# covid-respirator-ProtoB.net
KiCad netlist of a schematic drawn in EAGLE
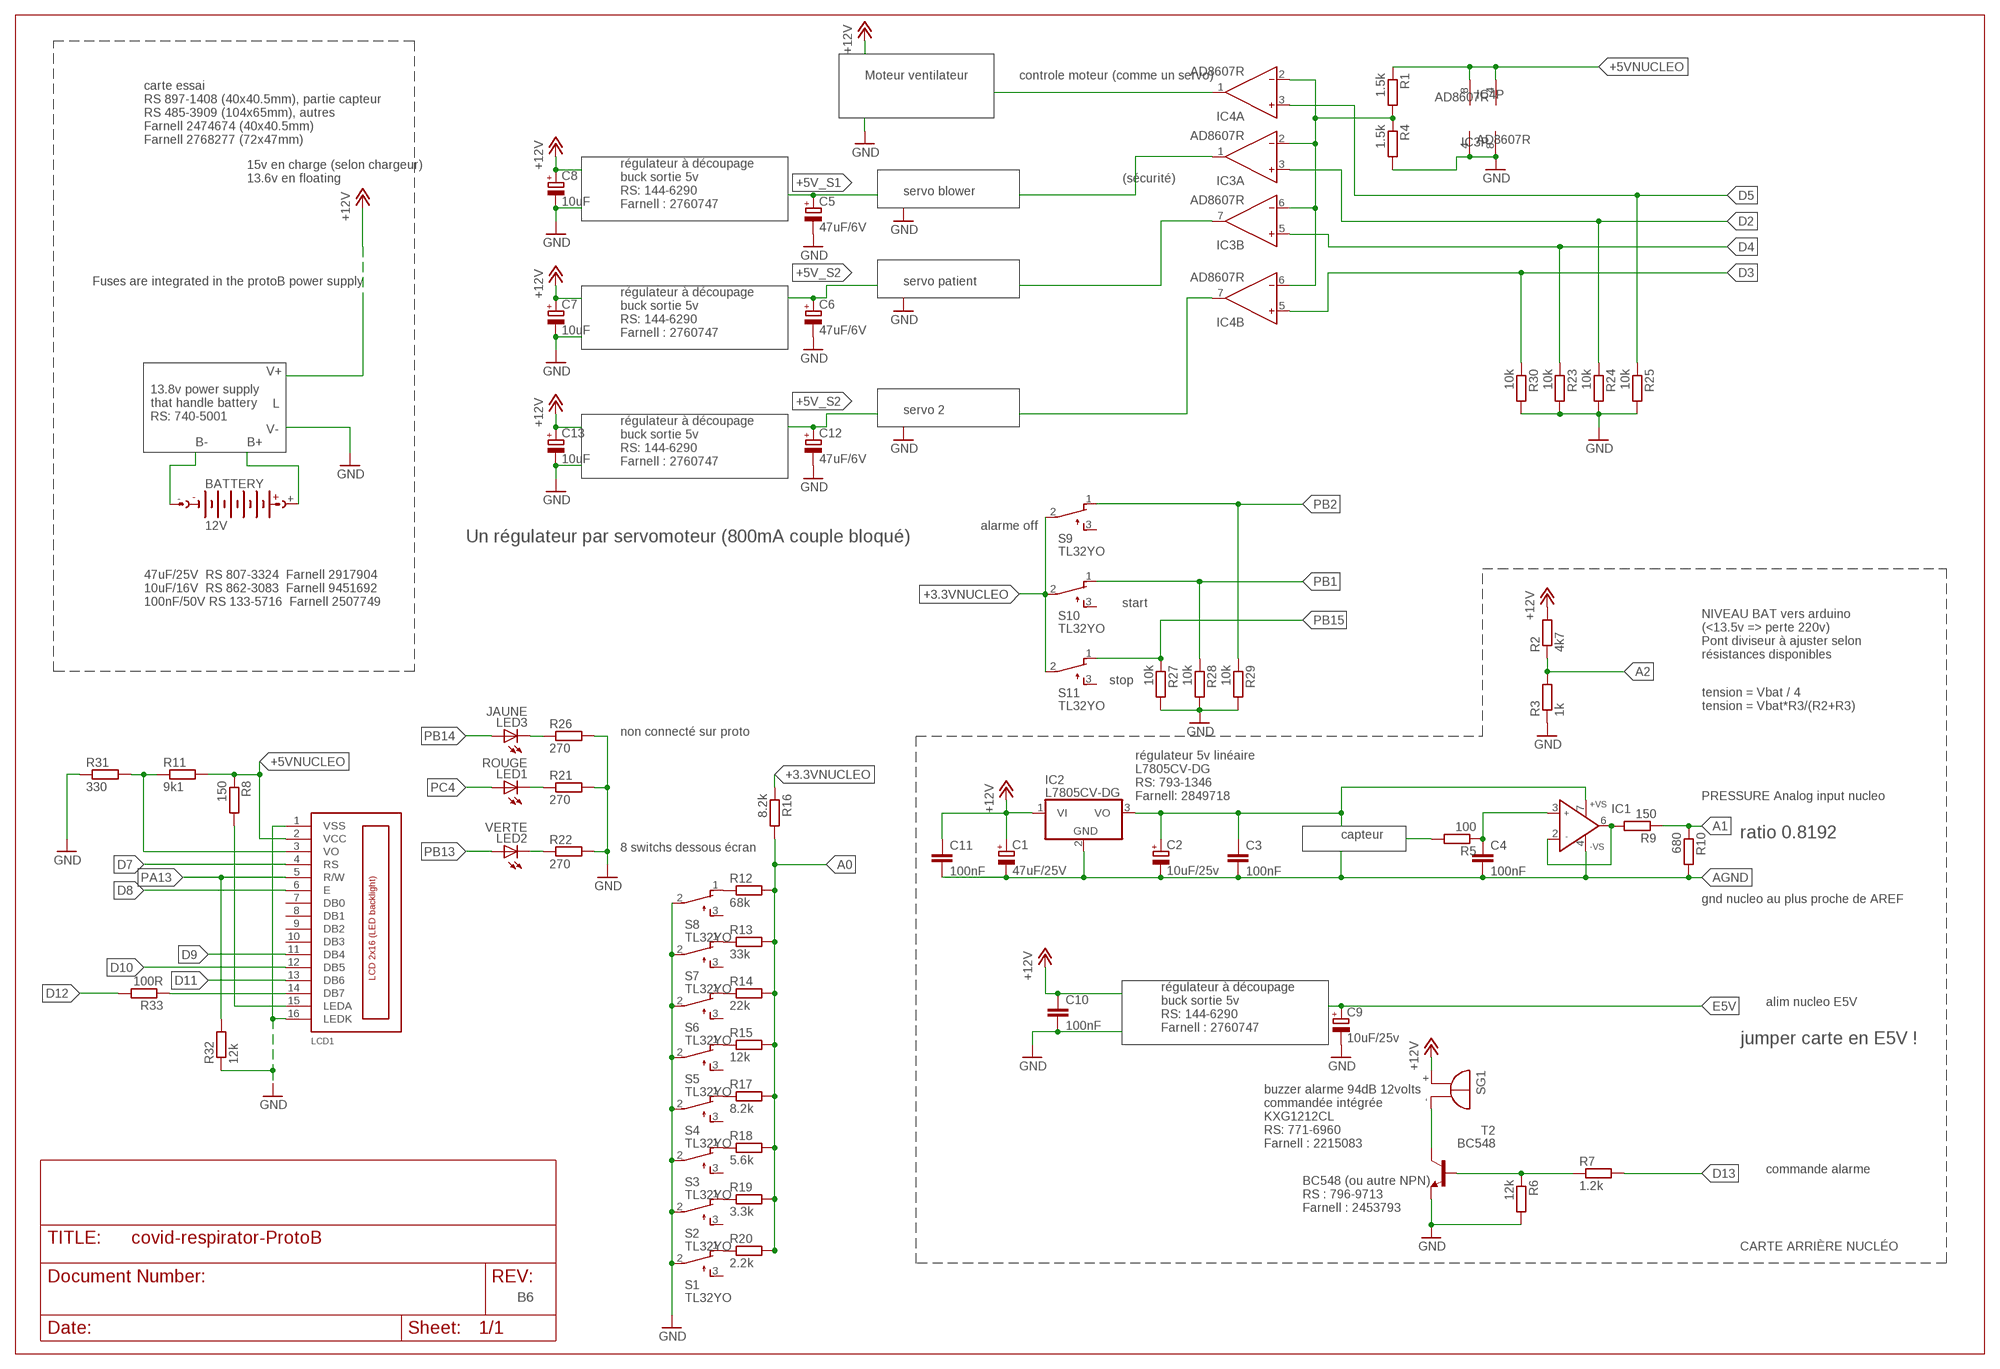
[diagram p0: schematic, sheet 1]

(export (version "E")
  (design (tool "Eeschema 10.0.6"))
  (components
    (comp (ref "BATTERY")
      (value "12V")
      (footprint "eagle-import:AB9V")
      (libsource (lib "eagle-import") (part "AB9V"))
    )
    (comp (ref "C1")
      (value "47uF/25V")
      (footprint "eagle-import:150CLZ-1010")
      (libsource (lib "eagle-import") (part "CPOL-EU150CLZ-1010"))
    )
    (comp (ref "C2")
      (value "10uF/25v")
      (footprint "eagle-import:150CLZ-1010")
      (libsource (lib "eagle-import") (part "CPOL-EU150CLZ-1010"))
    )
    (comp (ref "C3")
      (value "100nF")
      (footprint "eagle-import:C050-050X075")
      (libsource (lib "eagle-import") (part "C-EU050-050X075"))
    )
    (comp (ref "C4")
      (value "100nF")
      (footprint "eagle-import:C050-050X075")
      (libsource (lib "eagle-import") (part "C-EU050-050X075"))
    )
    (comp (ref "C5")
      (value "47uF/6V")
      (footprint "eagle-import:150CLZ-1010")
      (libsource (lib "eagle-import") (part "CPOL-EU150CLZ-1010"))
    )
    (comp (ref "C6")
      (value "47uF/6V")
      (footprint "eagle-import:150CLZ-1010")
      (libsource (lib "eagle-import") (part "CPOL-EU150CLZ-1010"))
    )
    (comp (ref "C7")
      (value "10uF")
      (footprint "eagle-import:150CLZ-1010")
      (libsource (lib "eagle-import") (part "CPOL-EU150CLZ-1010"))
    )
    (comp (ref "C8")
      (value "10uF")
      (footprint "eagle-import:150CLZ-1010")
      (libsource (lib "eagle-import") (part "CPOL-EU150CLZ-1010"))
    )
    (comp (ref "C9")
      (value "10uF/25v")
      (footprint "eagle-import:150CLZ-1010")
      (libsource (lib "eagle-import") (part "CPOL-EU150CLZ-1010"))
    )
    (comp (ref "C10")
      (value "100nF")
      (footprint "eagle-import:C050-050X075")
      (libsource (lib "eagle-import") (part "C-EU050-050X075"))
    )
    (comp (ref "C11")
      (value "100nF")
      (footprint "eagle-import:C050-050X075")
      (libsource (lib "eagle-import") (part "C-EU050-050X075"))
    )
    (comp (ref "C12")
      (value "47uF/6V")
      (footprint "eagle-import:150CLZ-1010")
      (libsource (lib "eagle-import") (part "CPOL-EU150CLZ-1010"))
    )
    (comp (ref "C13")
      (value "10uF")
      (footprint "eagle-import:150CLZ-1010")
      (libsource (lib "eagle-import") (part "CPOL-EU150CLZ-1010"))
    )
    (comp (ref "IC1")
      (value "AD825R")
      (footprint "eagle-import:SO8")
      (fields (field (name "MF") "ALTERA CORPORATION") (field (name "MPN") "AD825ARZ"))
      (libsource (lib "eagle-import") (part "AD825R"))
    )
    (comp (ref "IC2")
      (value "L7805CV-DG")
      (footprint "eagle-import:TO220H")
      (libsource (lib "eagle-import") (part "78T05"))
    )
    (comp (ref "IC3")
      (value "AD8607R")
      (footprint "eagle-import:SO8")
      (fields (field (name "MPN") "AD8607ARMZ-R2"))
      (libsource (lib "eagle-import") (part "AD8607R"))
    )
    (comp (ref "IC4")
      (value "AD8607R")
      (footprint "eagle-import:SO8")
      (fields (field (name "MPN") "AD8607ARMZ-R2"))
      (libsource (lib "eagle-import") (part "AD8607R"))
    )
    (comp (ref "LCD1")
      (value "LCD_2X16_SIL")
      (footprint "eagle-import:HY-1602F")
      (libsource (lib "eagle-import") (part "LCD_2X16_SIL"))
    )
    (comp (ref "LED1")
      (value "ROUGE")
      (footprint "eagle-import:LED3MM")
      (libsource (lib "eagle-import") (part "LED3MM"))
    )
    (comp (ref "LED2")
      (value "VERTE")
      (footprint "eagle-import:LED3MM")
      (libsource (lib "eagle-import") (part "LED3MM"))
    )
    (comp (ref "LED3")
      (value "JAUNE")
      (footprint "eagle-import:LED3MM")
      (libsource (lib "eagle-import") (part "LED3MM"))
    )
    (comp (ref "R1")
      (value "1.5k")
      (footprint "eagle-import:0207_10")
      (libsource (lib "eagle-import") (part "R-EU_0207/10"))
    )
    (comp (ref "R2")
      (value "4k7")
      (footprint "eagle-import:0207_10")
      (libsource (lib "eagle-import") (part "R-EU_0207/10"))
    )
    (comp (ref "R3")
      (value "1k")
      (footprint "eagle-import:0207_10")
      (libsource (lib "eagle-import") (part "R-EU_0207/10"))
    )
    (comp (ref "R4")
      (value "1.5k")
      (footprint "eagle-import:0207_10")
      (libsource (lib "eagle-import") (part "R-EU_0207/10"))
    )
    (comp (ref "R5")
      (value "100")
      (footprint "eagle-import:0207_10")
      (libsource (lib "eagle-import") (part "R-EU_0207/10"))
    )
    (comp (ref "R6")
      (value "12k")
      (footprint "eagle-import:0207_10")
      (libsource (lib "eagle-import") (part "R-EU_0207/10"))
    )
    (comp (ref "R7")
      (value "1.2k")
      (footprint "eagle-import:0207_10")
      (libsource (lib "eagle-import") (part "R-EU_0207/10"))
    )
    (comp (ref "R8")
      (value "150")
      (footprint "eagle-import:0207_10")
      (libsource (lib "eagle-import") (part "R-EU_0207/10"))
    )
    (comp (ref "R9")
      (value "150")
      (footprint "eagle-import:0207_10")
      (libsource (lib "eagle-import") (part "R-EU_0207/10"))
    )
    (comp (ref "R10")
      (value "680")
      (footprint "eagle-import:0207_10")
      (libsource (lib "eagle-import") (part "R-EU_0207/10"))
    )
    (comp (ref "R11")
      (value "9k1")
      (footprint "eagle-import:0207_10")
      (libsource (lib "eagle-import") (part "R-EU_0207/10"))
    )
    (comp (ref "R12")
      (value "68k")
      (footprint "eagle-import:0207_10")
      (libsource (lib "eagle-import") (part "R-EU_0207/10"))
    )
    (comp (ref "R13")
      (value "33k")
      (footprint "eagle-import:0207_10")
      (libsource (lib "eagle-import") (part "R-EU_0207/10"))
    )
    (comp (ref "R14")
      (value "22k")
      (footprint "eagle-import:0207_10")
      (libsource (lib "eagle-import") (part "R-EU_0207/10"))
    )
    (comp (ref "R15")
      (value "12k")
      (footprint "eagle-import:0207_10")
      (libsource (lib "eagle-import") (part "R-EU_0207/10"))
    )
    (comp (ref "R16")
      (value "8.2k")
      (footprint "eagle-import:0207_10")
      (libsource (lib "eagle-import") (part "R-EU_0207/10"))
    )
    (comp (ref "R17")
      (value "8.2k")
      (footprint "eagle-import:0207_10")
      (libsource (lib "eagle-import") (part "R-EU_0207/10"))
    )
    (comp (ref "R18")
      (value "5.6k")
      (footprint "eagle-import:0207_10")
      (libsource (lib "eagle-import") (part "R-EU_0207/10"))
    )
    (comp (ref "R19")
      (value "3.3k")
      (footprint "eagle-import:0207_10")
      (libsource (lib "eagle-import") (part "R-EU_0207/10"))
    )
    (comp (ref "R20")
      (value "2.2k")
      (footprint "eagle-import:0207_10")
      (libsource (lib "eagle-import") (part "R-EU_0207/10"))
    )
    (comp (ref "R21")
      (value "270")
      (footprint "eagle-import:0207_10")
      (libsource (lib "eagle-import") (part "R-EU_0207/10"))
    )
    (comp (ref "R22")
      (value "270")
      (footprint "eagle-import:0207_10")
      (libsource (lib "eagle-import") (part "R-EU_0207/10"))
    )
    (comp (ref "R23")
      (value "10k")
      (footprint "eagle-import:0207_10")
      (libsource (lib "eagle-import") (part "R-EU_0207/10"))
    )
    (comp (ref "R24")
      (value "10k")
      (footprint "eagle-import:0207_10")
      (libsource (lib "eagle-import") (part "R-EU_0207/10"))
    )
    (comp (ref "R25")
      (value "10k")
      (footprint "eagle-import:0207_10")
      (libsource (lib "eagle-import") (part "R-EU_0207/10"))
    )
    (comp (ref "R26")
      (value "270")
      (footprint "eagle-import:0207_10")
      (libsource (lib "eagle-import") (part "R-EU_0207/10"))
    )
    (comp (ref "R27")
      (value "10k")
      (footprint "eagle-import:0207_10")
      (libsource (lib "eagle-import") (part "R-EU_0207/10"))
    )
    (comp (ref "R28")
      (value "10k")
      (footprint "eagle-import:0207_10")
      (libsource (lib "eagle-import") (part "R-EU_0207/10"))
    )
    (comp (ref "R29")
      (value "10k")
      (footprint "eagle-import:0207_10")
      (libsource (lib "eagle-import") (part "R-EU_0207/10"))
    )
    (comp (ref "R30")
      (value "10k")
      (footprint "eagle-import:0207_10")
      (libsource (lib "eagle-import") (part "R-EU_0207/10"))
    )
    (comp (ref "R31")
      (value "330")
      (footprint "eagle-import:0207_10")
      (libsource (lib "eagle-import") (part "R-EU_0207/10"))
    )
    (comp (ref "R32")
      (value "12k")
      (footprint "eagle-import:0207_10")
      (libsource (lib "eagle-import") (part "R-EU_0207/10"))
    )
    (comp (ref "R33")
      (value "100R")
      (footprint "eagle-import:0207_10")
      (libsource (lib "eagle-import") (part "R-EU_0207/10"))
    )
    (comp (ref "S1")
      (value "TL32YO")
      (footprint "eagle-import:TL3XYO")
      (libsource (lib "eagle-import") (part "TL32YO"))
    )
    (comp (ref "S2")
      (value "TL32YO")
      (footprint "eagle-import:TL3XYO")
      (libsource (lib "eagle-import") (part "TL32YO"))
    )
    (comp (ref "S3")
      (value "TL32YO")
      (footprint "eagle-import:TL3XYO")
      (libsource (lib "eagle-import") (part "TL32YO"))
    )
    (comp (ref "S4")
      (value "TL32YO")
      (footprint "eagle-import:TL3XYO")
      (libsource (lib "eagle-import") (part "TL32YO"))
    )
    (comp (ref "S5")
      (value "TL32YO")
      (footprint "eagle-import:TL3XYO")
      (libsource (lib "eagle-import") (part "TL32YO"))
    )
    (comp (ref "S6")
      (value "TL32YO")
      (footprint "eagle-import:TL3XYO")
      (libsource (lib "eagle-import") (part "TL32YO"))
    )
    (comp (ref "S7")
      (value "TL32YO")
      (footprint "eagle-import:TL3XYO")
      (libsource (lib "eagle-import") (part "TL32YO"))
    )
    (comp (ref "S8")
      (value "TL32YO")
      (footprint "eagle-import:TL3XYO")
      (libsource (lib "eagle-import") (part "TL32YO"))
    )
    (comp (ref "S9")
      (value "TL32YO")
      (footprint "eagle-import:TL3XYO")
      (libsource (lib "eagle-import") (part "TL32YO"))
    )
    (comp (ref "S10")
      (value "TL32YO")
      (footprint "eagle-import:TL3XYO")
      (libsource (lib "eagle-import") (part "TL32YO"))
    )
    (comp (ref "S11")
      (value "TL32YO")
      (footprint "eagle-import:TL3XYO")
      (libsource (lib "eagle-import") (part "TL32YO"))
    )
    (comp (ref "SG1")
      (value "F/EB20P")
      (footprint "eagle-import:F_EB20P")
      (libsource (lib "eagle-import") (part "F/EB20P"))
    )
    (comp (ref "T2")
      (value "BC548")
      (footprint "eagle-import:TO92-CBE")
      (libsource (lib "eagle-import") (part "-NPN-TO92-CBEBC548"))
    )
  )
  (nets
    (net (code "1") (name "+3.3VNUCLEO") (class "Default")
      (node (ref "R16") (pin "1") (pinfunction "1_1") (pintype "passive"))
      (node (ref "S10") (pin "2") (pinfunction "P_2") (pintype "passive"))
      (node (ref "S11") (pin "2") (pinfunction "P_2") (pintype "passive"))
      (node (ref "S9") (pin "2") (pinfunction "P_2") (pintype "passive"))
    )
    (net (code "2") (name "+5VNUCLEO") (class "Default")
      (node (ref "IC3") (pin "4") (pinfunction "V-_4") (pintype "power_in"))
      (node (ref "IC4") (pin "8") (pinfunction "V+_8") (pintype "power_in"))
      (node (ref "LCD1") (pin "2") (pinfunction "VCC_2") (pintype "power_in"))
      (node (ref "R1") (pin "1") (pinfunction "1_1") (pintype "passive"))
      (node (ref "R11") (pin "2") (pinfunction "2_2") (pintype "passive"))
      (node (ref "R8") (pin "1") (pinfunction "1_1") (pintype "passive"))
    )
    (net (code "3") (name "+5V_S1") (class "Default")
      (node (ref "C5") (pin "+") (pinfunction "+_+") (pintype "passive"))
    )
    (net (code "4") (name "+5V_S2") (class "Default")
      (node (ref "C12") (pin "+") (pinfunction "+_+") (pintype "passive"))
      (node (ref "C6") (pin "+") (pinfunction "+_+") (pintype "passive"))
    )
    (net (code "5") (name "+12V") (class "Default")
      (node (ref "C1") (pin "+") (pinfunction "+_+") (pintype "passive"))
      (node (ref "C10") (pin "1") (pinfunction "1_1") (pintype "passive"))
      (node (ref "C11") (pin "1") (pinfunction "1_1") (pintype "passive"))
      (node (ref "C13") (pin "+") (pinfunction "+_+") (pintype "passive"))
      (node (ref "C7") (pin "+") (pinfunction "+_+") (pintype "passive"))
      (node (ref "C8") (pin "+") (pinfunction "+_+") (pintype "passive"))
      (node (ref "IC2") (pin "1") (pinfunction "VI_1") (pintype "input"))
      (node (ref "R2") (pin "2") (pinfunction "2_2") (pintype "passive"))
      (node (ref "SG1") (pin "+") (pinfunction "+_+") (pintype "passive"))
    )
    (net (code "6") (name "A0") (class "Default")
      (node (ref "R12") (pin "2") (pinfunction "2_2") (pintype "passive"))
      (node (ref "R13") (pin "2") (pinfunction "2_2") (pintype "passive"))
      (node (ref "R14") (pin "2") (pinfunction "2_2") (pintype "passive"))
      (node (ref "R15") (pin "2") (pinfunction "2_2") (pintype "passive"))
      (node (ref "R16") (pin "2") (pinfunction "2_2") (pintype "passive"))
      (node (ref "R17") (pin "2") (pinfunction "2_2") (pintype "passive"))
      (node (ref "R18") (pin "2") (pinfunction "2_2") (pintype "passive"))
      (node (ref "R19") (pin "2") (pinfunction "2_2") (pintype "passive"))
      (node (ref "R20") (pin "2") (pinfunction "2_2") (pintype "passive"))
    )
    (net (code "7") (name "A1") (class "Default")
      (node (ref "R10") (pin "1") (pinfunction "1_1") (pintype "passive"))
      (node (ref "R9") (pin "1") (pinfunction "1_1") (pintype "passive"))
    )
    (net (code "8") (name "A2") (class "Default")
      (node (ref "R2") (pin "1") (pinfunction "1_1") (pintype "passive"))
      (node (ref "R3") (pin "2") (pinfunction "2_2") (pintype "passive"))
    )
    (net (code "9") (name "AGND") (class "Default")
      (node (ref "C1") (pin "-") (pinfunction "-_-") (pintype "passive"))
      (node (ref "C11") (pin "2") (pinfunction "2_2") (pintype "passive"))
      (node (ref "C2") (pin "-") (pinfunction "-_-") (pintype "passive"))
      (node (ref "C3") (pin "2") (pinfunction "2_2") (pintype "passive"))
      (node (ref "C4") (pin "2") (pinfunction "2_2") (pintype "passive"))
      (node (ref "IC1") (pin "4") (pinfunction "-VS_4") (pintype "input"))
      (node (ref "IC2") (pin "2") (pinfunction "GND_2") (pintype "passive"))
      (node (ref "R10") (pin "2") (pinfunction "2_2") (pintype "passive"))
    )
    (net (code "10") (name "D2") (class "Default")
      (node (ref "IC3") (pin "3") (pinfunction "IN+_3") (pintype "input"))
      (node (ref "R24") (pin "1") (pinfunction "1_1") (pintype "passive"))
    )
    (net (code "11") (name "D3") (class "Default")
      (node (ref "IC4") (pin "5") (pinfunction "IN+_5") (pintype "input"))
      (node (ref "R30") (pin "1") (pinfunction "1_1") (pintype "passive"))
    )
    (net (code "12") (name "D4") (class "Default")
      (node (ref "IC3") (pin "5") (pinfunction "IN+_5") (pintype "input"))
      (node (ref "R23") (pin "1") (pinfunction "1_1") (pintype "passive"))
    )
    (net (code "13") (name "D5") (class "Default")
      (node (ref "IC4") (pin "3") (pinfunction "IN+_3") (pintype "input"))
      (node (ref "R25") (pin "1") (pinfunction "1_1") (pintype "passive"))
    )
    (net (code "14") (name "D7") (class "Default")
      (node (ref "LCD1") (pin "4") (pinfunction "RS_4") (pintype "input"))
    )
    (net (code "15") (name "D8") (class "Default")
      (node (ref "LCD1") (pin "6") (pinfunction "E_6") (pintype "input"))
    )
    (net (code "16") (name "D9") (class "Default")
      (node (ref "LCD1") (pin "11") (pinfunction "DB4_11") (pintype "bidirectional"))
    )
    (net (code "17") (name "D10") (class "Default")
      (node (ref "LCD1") (pin "12") (pinfunction "DB5_12") (pintype "bidirectional"))
    )
    (net (code "18") (name "D11") (class "Default")
      (node (ref "LCD1") (pin "13") (pinfunction "DB6_13") (pintype "bidirectional"))
    )
    (net (code "19") (name "D12") (class "Default")
      (node (ref "R33") (pin "2") (pinfunction "2_2") (pintype "passive"))
    )
    (net (code "20") (name "D13") (class "Default")
      (node (ref "R7") (pin "2") (pinfunction "2_2") (pintype "passive"))
    )
    (net (code "21") (name "E5V") (class "Default")
      (node (ref "C9") (pin "+") (pinfunction "+_+") (pintype "passive"))
    )
    (net (code "22") (name "GND") (class "Default")
      (node (ref "C10") (pin "2") (pinfunction "2_2") (pintype "passive"))
      (node (ref "C12") (pin "-") (pinfunction "-_-") (pintype "passive"))
      (node (ref "C13") (pin "-") (pinfunction "-_-") (pintype "passive"))
      (node (ref "C5") (pin "-") (pinfunction "-_-") (pintype "passive"))
      (node (ref "C6") (pin "-") (pinfunction "-_-") (pintype "passive"))
      (node (ref "C7") (pin "-") (pinfunction "-_-") (pintype "passive"))
      (node (ref "C8") (pin "-") (pinfunction "-_-") (pintype "passive"))
      (node (ref "C9") (pin "-") (pinfunction "-_-") (pintype "passive"))
      (node (ref "IC3") (pin "8") (pinfunction "V+_8") (pintype "power_in"))
      (node (ref "IC4") (pin "4") (pinfunction "V-_4") (pintype "power_in"))
      (node (ref "LCD1") (pin "1") (pinfunction "VSS_1") (pintype "power_in"))
      (node (ref "LCD1") (pin "16") (pinfunction "LEDK_16") (pintype "passive"))
      (node (ref "R21") (pin "2") (pinfunction "2_2") (pintype "passive"))
      (node (ref "R22") (pin "2") (pinfunction "2_2") (pintype "passive"))
      (node (ref "R23") (pin "2") (pinfunction "2_2") (pintype "passive"))
      (node (ref "R24") (pin "2") (pinfunction "2_2") (pintype "passive"))
      (node (ref "R25") (pin "2") (pinfunction "2_2") (pintype "passive"))
      (node (ref "R26") (pin "2") (pinfunction "2_2") (pintype "passive"))
      (node (ref "R27") (pin "2") (pinfunction "2_2") (pintype "passive"))
      (node (ref "R28") (pin "2") (pinfunction "2_2") (pintype "passive"))
      (node (ref "R29") (pin "2") (pinfunction "2_2") (pintype "passive"))
      (node (ref "R3") (pin "1") (pinfunction "1_1") (pintype "passive"))
      (node (ref "R30") (pin "2") (pinfunction "2_2") (pintype "passive"))
      (node (ref "R31") (pin "1") (pinfunction "1_1") (pintype "passive"))
      (node (ref "R32") (pin "1") (pinfunction "1_1") (pintype "passive"))
      (node (ref "R4") (pin "2") (pinfunction "2_2") (pintype "passive"))
      (node (ref "R6") (pin "2") (pinfunction "2_2") (pintype "passive"))
      (node (ref "S1") (pin "2") (pinfunction "P_2") (pintype "passive"))
      (node (ref "S2") (pin "2") (pinfunction "P_2") (pintype "passive"))
      (node (ref "S3") (pin "2") (pinfunction "P_2") (pintype "passive"))
      (node (ref "S4") (pin "2") (pinfunction "P_2") (pintype "passive"))
      (node (ref "S5") (pin "2") (pinfunction "P_2") (pintype "passive"))
      (node (ref "S6") (pin "2") (pinfunction "P_2") (pintype "passive"))
      (node (ref "S7") (pin "2") (pinfunction "P_2") (pintype "passive"))
      (node (ref "S8") (pin "2") (pinfunction "P_2") (pintype "passive"))
      (node (ref "T2") (pin "E") (pinfunction "E_E") (pintype "passive"))
    )
    (net (code "23") (name "Net-(IC1-+VS)") (class "Default")
      (node (ref "C2") (pin "+") (pinfunction "+_+") (pintype "passive"))
      (node (ref "C3") (pin "1") (pinfunction "1_1") (pintype "passive"))
      (node (ref "IC1") (pin "7") (pinfunction "+VS_7") (pintype "input"))
      (node (ref "IC2") (pin "3") (pinfunction "VO_3") (pintype "passive"))
    )
    (net (code "24") (name "Net-(IC1-IN+)") (class "Default")
      (node (ref "C4") (pin "1") (pinfunction "1_1") (pintype "passive"))
      (node (ref "IC1") (pin "3") (pinfunction "IN+_3") (pintype "input"))
      (node (ref "R5") (pin "1") (pinfunction "1_1") (pintype "passive"))
    )
    (net (code "25") (name "Net-(IC1-IN-)") (class "Default")
      (node (ref "IC1") (pin "2") (pinfunction "IN-_2") (pintype "input"))
      (node (ref "IC1") (pin "6") (pinfunction "OUT_6") (pintype "output"))
      (node (ref "R9") (pin "2") (pinfunction "2_2") (pintype "passive"))
    )
    (net (code "26") (name "Net-(IC3A-IN-)") (class "Default")
      (node (ref "IC3") (pin "2") (pinfunction "IN-_2") (pintype "input"))
      (node (ref "IC3") (pin "6") (pinfunction "IN-_6") (pintype "input"))
      (node (ref "IC4") (pin "2") (pinfunction "IN-_2") (pintype "input"))
      (node (ref "IC4") (pin "6") (pinfunction "IN-_6") (pintype "input"))
      (node (ref "R1") (pin "2") (pinfunction "2_2") (pintype "passive"))
      (node (ref "R4") (pin "1") (pinfunction "1_1") (pintype "passive"))
    )
    (net (code "27") (name "Net-(LCD1-DB7)") (class "Default")
      (node (ref "LCD1") (pin "14") (pinfunction "DB7_14") (pintype "bidirectional"))
      (node (ref "R33") (pin "1") (pinfunction "1_1") (pintype "passive"))
    )
    (net (code "28") (name "Net-(LCD1-LEDA)") (class "Default")
      (node (ref "LCD1") (pin "15") (pinfunction "LEDA_15") (pintype "passive"))
      (node (ref "R8") (pin "2") (pinfunction "2_2") (pintype "passive"))
    )
    (net (code "29") (name "Net-(LCD1-VO)") (class "Default")
      (node (ref "LCD1") (pin "3") (pinfunction "VO_3") (pintype "input"))
      (node (ref "R11") (pin "1") (pinfunction "1_1") (pintype "passive"))
      (node (ref "R31") (pin "2") (pinfunction "2_2") (pintype "passive"))
    )
    (net (code "30") (name "Net-(LED1-C)") (class "Default")
      (node (ref "LED1") (pin "K") (pinfunction "C_K") (pintype "passive"))
      (node (ref "R21") (pin "1") (pinfunction "1_1") (pintype "passive"))
    )
    (net (code "31") (name "Net-(LED2-C)") (class "Default")
      (node (ref "LED2") (pin "K") (pinfunction "C_K") (pintype "passive"))
      (node (ref "R22") (pin "1") (pinfunction "1_1") (pintype "passive"))
    )
    (net (code "32") (name "Net-(LED3-C)") (class "Default")
      (node (ref "LED3") (pin "K") (pinfunction "C_K") (pintype "passive"))
      (node (ref "R26") (pin "1") (pinfunction "1_1") (pintype "passive"))
    )
    (net (code "33") (name "Net-(R6-Pad1)") (class "Default")
      (node (ref "R6") (pin "1") (pinfunction "1_1") (pintype "passive"))
      (node (ref "R7") (pin "1") (pinfunction "1_1") (pintype "passive"))
      (node (ref "T2") (pin "B") (pinfunction "B_B") (pintype "passive"))
    )
    (net (code "34") (name "Net-(S1-O)") (class "Default")
      (node (ref "R20") (pin "1") (pinfunction "1_1") (pintype "passive"))
      (node (ref "S1") (pin "1") (pinfunction "O_1") (pintype "passive"))
    )
    (net (code "35") (name "Net-(S2-O)") (class "Default")
      (node (ref "R19") (pin "1") (pinfunction "1_1") (pintype "passive"))
      (node (ref "S2") (pin "1") (pinfunction "O_1") (pintype "passive"))
    )
    (net (code "36") (name "Net-(S3-O)") (class "Default")
      (node (ref "R18") (pin "1") (pinfunction "1_1") (pintype "passive"))
      (node (ref "S3") (pin "1") (pinfunction "O_1") (pintype "passive"))
    )
    (net (code "37") (name "Net-(S4-O)") (class "Default")
      (node (ref "R17") (pin "1") (pinfunction "1_1") (pintype "passive"))
      (node (ref "S4") (pin "1") (pinfunction "O_1") (pintype "passive"))
    )
    (net (code "38") (name "Net-(S5-O)") (class "Default")
      (node (ref "R15") (pin "1") (pinfunction "1_1") (pintype "passive"))
      (node (ref "S5") (pin "1") (pinfunction "O_1") (pintype "passive"))
    )
    (net (code "39") (name "Net-(S6-O)") (class "Default")
      (node (ref "R14") (pin "1") (pinfunction "1_1") (pintype "passive"))
      (node (ref "S6") (pin "1") (pinfunction "O_1") (pintype "passive"))
    )
    (net (code "40") (name "Net-(S7-O)") (class "Default")
      (node (ref "R13") (pin "1") (pinfunction "1_1") (pintype "passive"))
      (node (ref "S7") (pin "1") (pinfunction "O_1") (pintype "passive"))
    )
    (net (code "41") (name "Net-(S8-O)") (class "Default")
      (node (ref "R12") (pin "1") (pinfunction "1_1") (pintype "passive"))
      (node (ref "S8") (pin "1") (pinfunction "O_1") (pintype "passive"))
    )
    (net (code "42") (name "Net-(SG1-Pad-)") (class "Default")
      (node (ref "SG1") (pin "-") (pinfunction "-_-") (pintype "passive"))
      (node (ref "T2") (pin "C") (pinfunction "C_C") (pintype "passive"))
    )
    (net (code "43") (name "PA13") (class "Default")
      (node (ref "LCD1") (pin "5") (pinfunction "R/W_5") (pintype "input"))
      (node (ref "R32") (pin "2") (pinfunction "2_2") (pintype "passive"))
    )
    (net (code "44") (name "PB1") (class "Default")
      (node (ref "R28") (pin "1") (pinfunction "1_1") (pintype "passive"))
      (node (ref "S10") (pin "1") (pinfunction "O_1") (pintype "passive"))
    )
    (net (code "45") (name "PB2") (class "Default")
      (node (ref "R29") (pin "1") (pinfunction "1_1") (pintype "passive"))
      (node (ref "S9") (pin "1") (pinfunction "O_1") (pintype "passive"))
    )
    (net (code "46") (name "PB13") (class "Default")
      (node (ref "LED2") (pin "A") (pinfunction "A_A") (pintype "passive"))
    )
    (net (code "47") (name "PB14") (class "Default")
      (node (ref "LED3") (pin "A") (pinfunction "A_A") (pintype "passive"))
    )
    (net (code "48") (name "PB15") (class "Default")
      (node (ref "R27") (pin "1") (pinfunction "1_1") (pintype "passive"))
      (node (ref "S11") (pin "1") (pinfunction "O_1") (pintype "passive"))
    )
    (net (code "49") (name "PC4") (class "Default")
      (node (ref "LED1") (pin "A") (pinfunction "A_A") (pintype "passive"))
    )
    (net (code "50") (name "unconnected-(BATTERY-Pad+)") (class "Default")
      (node (ref "BATTERY") (pin "+") (pinfunction "+_+") (pintype "passive"))
    )
    (net (code "51") (name "unconnected-(BATTERY-Pad-)") (class "Default")
      (node (ref "BATTERY") (pin "-") (pinfunction "-_-") (pintype "passive"))
    )
    (net (code "52") (name "unconnected-(IC3A-OUT-Pad1)") (class "Default")
      (node (ref "IC3") (pin "1") (pinfunction "OUT_1") (pintype "output"))
    )
    (net (code "53") (name "unconnected-(IC3B-OUT-Pad7)") (class "Default")
      (node (ref "IC3") (pin "7") (pinfunction "OUT_7") (pintype "output"))
    )
    (net (code "54") (name "unconnected-(IC4A-OUT-Pad1)") (class "Default")
      (node (ref "IC4") (pin "1") (pinfunction "OUT_1") (pintype "output"))
    )
    (net (code "55") (name "unconnected-(IC4B-OUT-Pad7)") (class "Default")
      (node (ref "IC4") (pin "7") (pinfunction "OUT_7") (pintype "output"))
    )
    (net (code "56") (name "unconnected-(LCD1-DB0-Pad7)") (class "Default")
      (node (ref "LCD1") (pin "7") (pinfunction "DB0_7") (pintype "bidirectional"))
    )
    (net (code "57") (name "unconnected-(LCD1-DB1-Pad8)") (class "Default")
      (node (ref "LCD1") (pin "8") (pinfunction "DB1_8") (pintype "bidirectional"))
    )
    (net (code "58") (name "unconnected-(LCD1-DB2-Pad9)") (class "Default")
      (node (ref "LCD1") (pin "9") (pinfunction "DB2_9") (pintype "bidirectional"))
    )
    (net (code "59") (name "unconnected-(LCD1-DB3-Pad10)") (class "Default")
      (node (ref "LCD1") (pin "10") (pinfunction "DB3_10") (pintype "bidirectional"))
    )
    (net (code "60") (name "unconnected-(R5-Pad2)") (class "Default")
      (node (ref "R5") (pin "2") (pinfunction "2_2") (pintype "passive"))
    )
    (net (code "61") (name "unconnected-(S1-S-Pad3)") (class "Default")
      (node (ref "S1") (pin "3") (pinfunction "S_3") (pintype "passive"))
    )
    (net (code "62") (name "unconnected-(S2-S-Pad3)") (class "Default")
      (node (ref "S2") (pin "3") (pinfunction "S_3") (pintype "passive"))
    )
    (net (code "63") (name "unconnected-(S3-S-Pad3)") (class "Default")
      (node (ref "S3") (pin "3") (pinfunction "S_3") (pintype "passive"))
    )
    (net (code "64") (name "unconnected-(S4-S-Pad3)") (class "Default")
      (node (ref "S4") (pin "3") (pinfunction "S_3") (pintype "passive"))
    )
    (net (code "65") (name "unconnected-(S5-S-Pad3)") (class "Default")
      (node (ref "S5") (pin "3") (pinfunction "S_3") (pintype "passive"))
    )
    (net (code "66") (name "unconnected-(S6-S-Pad3)") (class "Default")
      (node (ref "S6") (pin "3") (pinfunction "S_3") (pintype "passive"))
    )
    (net (code "67") (name "unconnected-(S7-S-Pad3)") (class "Default")
      (node (ref "S7") (pin "3") (pinfunction "S_3") (pintype "passive"))
    )
    (net (code "68") (name "unconnected-(S8-S-Pad3)") (class "Default")
      (node (ref "S8") (pin "3") (pinfunction "S_3") (pintype "passive"))
    )
    (net (code "69") (name "unconnected-(S9-S-Pad3)") (class "Default")
      (node (ref "S9") (pin "3") (pinfunction "S_3") (pintype "passive"))
    )
    (net (code "70") (name "unconnected-(S10-S-Pad3)") (class "Default")
      (node (ref "S10") (pin "3") (pinfunction "S_3") (pintype "passive"))
    )
    (net (code "71") (name "unconnected-(S11-S-Pad3)") (class "Default")
      (node (ref "S11") (pin "3") (pinfunction "S_3") (pintype "passive"))
    )
  )
)
